# control_board.net
KiCad netlist of a schematic drawn in EAGLE
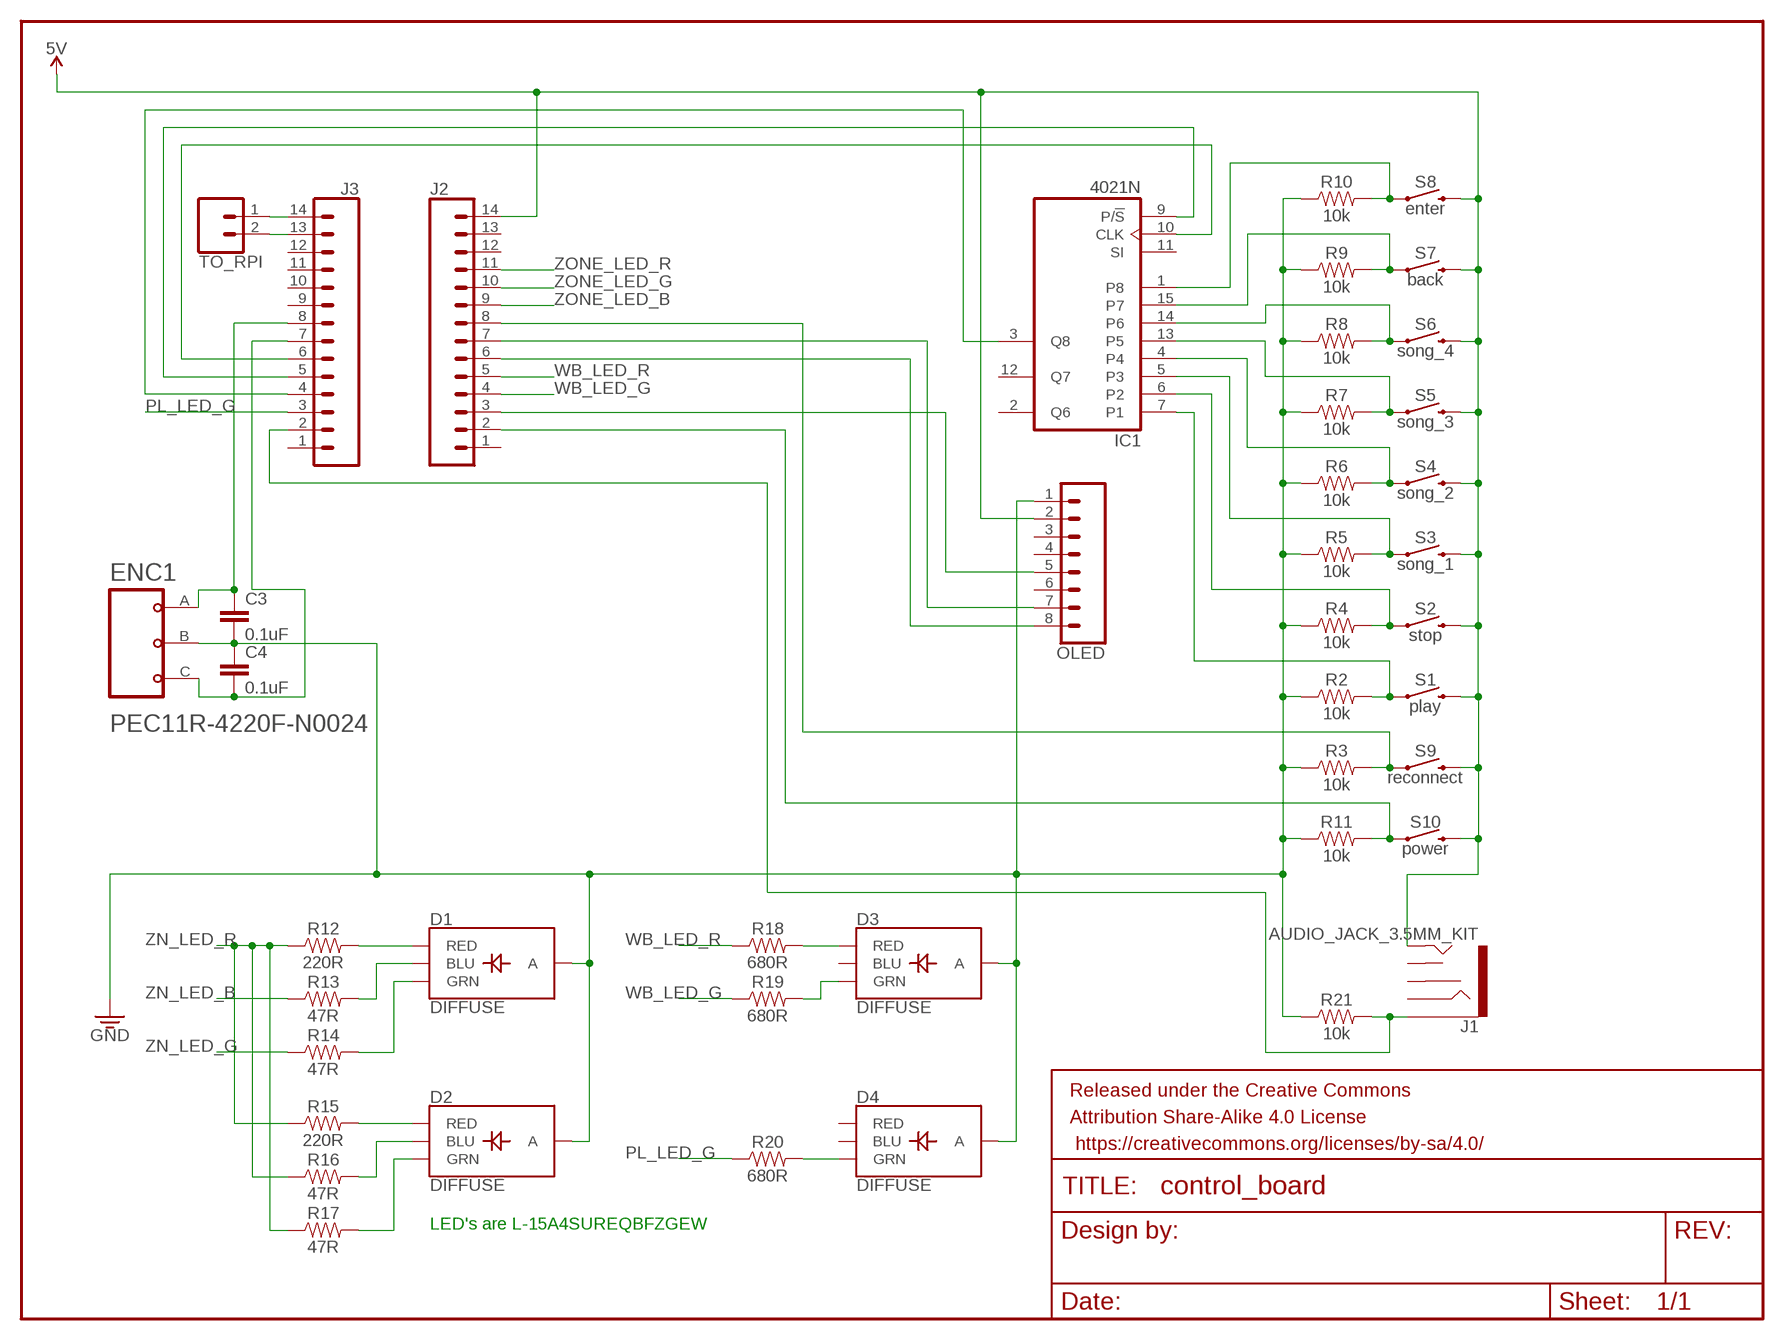
[diagram p0: schematic, sheet 1]

(export (version "E")
  (design (tool "Eeschema 10.0.6"))
  (components
    (comp (ref "C3")
      (value "0.1uF")
      (footprint "eagle-import:CAP-PTH-SMALL-KIT")
      (libsource (lib "eagle-import") (part "0.1UF-KIT-EZ-50V-20%"))
    )
    (comp (ref "C4")
      (value "0.1uF")
      (footprint "eagle-import:CAP-PTH-SMALL-KIT")
      (libsource (lib "eagle-import") (part "0.1UF-KIT-EZ-50V-20%"))
    )
    (comp (ref "D1")
      (value "DIFFUSE")
      (footprint "eagle-import:LED-RGB-THRU")
      (libsource (lib "eagle-import") (part "LED-RGB-CADIFFUSE"))
    )
    (comp (ref "D2")
      (value "DIFFUSE")
      (footprint "eagle-import:LED-RGB-THRU")
      (libsource (lib "eagle-import") (part "LED-RGB-CADIFFUSE"))
    )
    (comp (ref "D3")
      (value "DIFFUSE")
      (footprint "eagle-import:LED-RGB-THRU")
      (libsource (lib "eagle-import") (part "LED-RGB-CADIFFUSE"))
    )
    (comp (ref "D4")
      (value "DIFFUSE")
      (footprint "eagle-import:LED-RGB-THRU")
      (libsource (lib "eagle-import") (part "LED-RGB-CADIFFUSE"))
    )
    (comp (ref "ENC1")
      (value "PEC11R-4220F-N0024")
      (footprint "eagle-import:PEC11R-4220F-N0024")
      (libsource (lib "eagle-import") (part "PEC11R-4220F-N0024"))
    )
    (comp (ref "FRAME1")
      (value "FRAME-LETTER")
      (footprint "eagle-import:CREATIVE_COMMONS")
      (libsource (lib "eagle-import") (part "FRAME-LETTER"))
    )
    (comp (ref "IC1")
      (value "4021N")
      (footprint "eagle-import:DIL16")
      (libsource (lib "eagle-import") (part "4021N"))
    )
    (comp (ref "J1")
      (value "AUDIO_JACK_3.5MM_KIT")
      (footprint "eagle-import:AUDIO-JACK-KIT")
      (libsource (lib "eagle-import") (part "AUDIO_JACK_3.5MM_KIT"))
    )
    (comp (ref "J2")
      (value "CONN_14")
      (footprint "eagle-import:1X14")
      (libsource (lib "eagle-import") (part "CONN_14"))
    )
    (comp (ref "J3")
      (value "CONN_14")
      (footprint "eagle-import:1X14")
      (libsource (lib "eagle-import") (part "CONN_14"))
    )
    (comp (ref "OLED")
      (value "CONN_08\"")
      (footprint "eagle-import:1X08")
      (libsource (lib "eagle-import") (part "CONN_08{dblquote}"))
    )
    (comp (ref "R2")
      (value "10k")
      (footprint "eagle-import:AXIAL-0.3")
      (libsource (lib "eagle-import") (part "10KOHM-HORIZ-1/4W-1%"))
    )
    (comp (ref "R3")
      (value "10k")
      (footprint "eagle-import:AXIAL-0.3")
      (libsource (lib "eagle-import") (part "10KOHM-HORIZ-1/4W-1%"))
    )
    (comp (ref "R4")
      (value "10k")
      (footprint "eagle-import:AXIAL-0.3")
      (libsource (lib "eagle-import") (part "10KOHM-HORIZ-1/4W-1%"))
    )
    (comp (ref "R5")
      (value "10k")
      (footprint "eagle-import:AXIAL-0.3")
      (libsource (lib "eagle-import") (part "10KOHM-HORIZ-1/4W-1%"))
    )
    (comp (ref "R6")
      (value "10k")
      (footprint "eagle-import:AXIAL-0.3")
      (libsource (lib "eagle-import") (part "10KOHM-HORIZ-1/4W-1%"))
    )
    (comp (ref "R7")
      (value "10k")
      (footprint "eagle-import:AXIAL-0.3")
      (libsource (lib "eagle-import") (part "10KOHM-HORIZ-1/4W-1%"))
    )
    (comp (ref "R8")
      (value "10k")
      (footprint "eagle-import:AXIAL-0.3")
      (libsource (lib "eagle-import") (part "10KOHM-HORIZ-1/4W-1%"))
    )
    (comp (ref "R9")
      (value "10k")
      (footprint "eagle-import:AXIAL-0.3")
      (libsource (lib "eagle-import") (part "10KOHM-HORIZ-1/4W-1%"))
    )
    (comp (ref "R10")
      (value "10k")
      (footprint "eagle-import:AXIAL-0.3")
      (libsource (lib "eagle-import") (part "10KOHM-HORIZ-1/4W-1%"))
    )
    (comp (ref "R11")
      (value "10k")
      (footprint "eagle-import:AXIAL-0.3")
      (libsource (lib "eagle-import") (part "10KOHM-HORIZ-1/4W-1%"))
    )
    (comp (ref "R12")
      (value "220R")
      (footprint "eagle-import:AXIAL-0.3")
      (libsource (lib "eagle-import") (part "100OHM-HORIZ-1/4W-1%"))
    )
    (comp (ref "R13")
      (value "47R")
      (footprint "eagle-import:AXIAL-0.3")
      (libsource (lib "eagle-import") (part "100OHM-HORIZ-1/4W-1%"))
    )
    (comp (ref "R14")
      (value "47R")
      (footprint "eagle-import:AXIAL-0.3")
      (libsource (lib "eagle-import") (part "100OHM-HORIZ-1/4W-1%"))
    )
    (comp (ref "R15")
      (value "220R")
      (footprint "eagle-import:AXIAL-0.3")
      (libsource (lib "eagle-import") (part "100OHM-HORIZ-1/4W-1%"))
    )
    (comp (ref "R16")
      (value "47R")
      (footprint "eagle-import:AXIAL-0.3")
      (libsource (lib "eagle-import") (part "100OHM-HORIZ-1/4W-1%"))
    )
    (comp (ref "R17")
      (value "47R")
      (footprint "eagle-import:AXIAL-0.3")
      (libsource (lib "eagle-import") (part "100OHM-HORIZ-1/4W-1%"))
    )
    (comp (ref "R18")
      (value "680R")
      (footprint "eagle-import:AXIAL-0.3")
      (libsource (lib "eagle-import") (part "100OHM-HORIZ-1/4W-1%"))
    )
    (comp (ref "R19")
      (value "680R")
      (footprint "eagle-import:AXIAL-0.3")
      (libsource (lib "eagle-import") (part "100OHM-HORIZ-1/4W-1%"))
    )
    (comp (ref "R20")
      (value "680R")
      (footprint "eagle-import:AXIAL-0.3")
      (libsource (lib "eagle-import") (part "100OHM-HORIZ-1/4W-1%"))
    )
    (comp (ref "R21")
      (value "10k")
      (footprint "eagle-import:AXIAL-0.3")
      (libsource (lib "eagle-import") (part "10KOHM-HORIZ-1/4W-1%"))
    )
    (comp (ref "S1")
      (value "play")
      (footprint "eagle-import:TACTILE_SWITCH_PTH_6.0MM")
      (libsource (lib "eagle-import") (part "MOMENTARY-SWITCH-SPST-PTH-6.0MM"))
    )
    (comp (ref "S2")
      (value "stop")
      (footprint "eagle-import:TACTILE_SWITCH_PTH_6.0MM")
      (libsource (lib "eagle-import") (part "MOMENTARY-SWITCH-SPST-PTH-6.0MM"))
    )
    (comp (ref "S3")
      (value "song_1")
      (footprint "eagle-import:TACTILE_SWITCH_PTH_6.0MM")
      (libsource (lib "eagle-import") (part "MOMENTARY-SWITCH-SPST-PTH-6.0MM"))
    )
    (comp (ref "S4")
      (value "song_2")
      (footprint "eagle-import:TACTILE_SWITCH_PTH_6.0MM")
      (libsource (lib "eagle-import") (part "MOMENTARY-SWITCH-SPST-PTH-6.0MM"))
    )
    (comp (ref "S5")
      (value "song_3")
      (footprint "eagle-import:TACTILE_SWITCH_PTH_6.0MM")
      (libsource (lib "eagle-import") (part "MOMENTARY-SWITCH-SPST-PTH-6.0MM"))
    )
    (comp (ref "S6")
      (value "song_4")
      (footprint "eagle-import:TACTILE_SWITCH_PTH_6.0MM")
      (libsource (lib "eagle-import") (part "MOMENTARY-SWITCH-SPST-PTH-6.0MM"))
    )
    (comp (ref "S7")
      (value "back")
      (footprint "eagle-import:TACTILE_SWITCH_PTH_6.0MM")
      (libsource (lib "eagle-import") (part "MOMENTARY-SWITCH-SPST-PTH-6.0MM"))
    )
    (comp (ref "S8")
      (value "enter")
      (footprint "eagle-import:TACTILE_SWITCH_PTH_6.0MM")
      (libsource (lib "eagle-import") (part "MOMENTARY-SWITCH-SPST-PTH-6.0MM"))
    )
    (comp (ref "S9")
      (value "reconnect")
      (footprint "eagle-import:TACTILE_SWITCH_PTH_6.0MM")
      (libsource (lib "eagle-import") (part "MOMENTARY-SWITCH-SPST-PTH-6.0MM"))
    )
    (comp (ref "S10")
      (value "power")
      (footprint "eagle-import:TACTILE_SWITCH_PTH_6.0MM")
      (libsource (lib "eagle-import") (part "MOMENTARY-SWITCH-SPST-PTH-6.0MM"))
    )
    (comp (ref "TO_RPI")
      (value "CONN_02")
      (footprint "eagle-import:1X02")
      (libsource (lib "eagle-import") (part "CONN_02"))
    )
  )
  (nets
    (net (code "1") (name "/PL_LED_G") (class "Default")
      (node (ref "J3") (pin "3") (pinfunction "3_3") (pintype "passive"))
      (node (ref "R20") (pin "P$1") (pinfunction "1_P$1") (pintype "passive"))
    )
    (net (code "2") (name "/WB_LED_G") (class "Default")
      (node (ref "J2") (pin "4") (pinfunction "4_4") (pintype "passive"))
      (node (ref "R19") (pin "P$1") (pinfunction "1_P$1") (pintype "passive"))
    )
    (net (code "3") (name "/WB_LED_R") (class "Default")
      (node (ref "J2") (pin "5") (pinfunction "5_5") (pintype "passive"))
      (node (ref "R18") (pin "P$1") (pinfunction "1_P$1") (pintype "passive"))
    )
    (net (code "4") (name "/ZN_LED_B") (class "Default")
      (node (ref "R13") (pin "P$1") (pinfunction "1_P$1") (pintype "passive"))
    )
    (net (code "5") (name "/ZN_LED_G") (class "Default")
      (node (ref "R14") (pin "P$1") (pinfunction "1_P$1") (pintype "passive"))
    )
    (net (code "6") (name "/ZN_LED_R") (class "Default")
      (node (ref "R12") (pin "P$1") (pinfunction "1_P$1") (pintype "passive"))
      (node (ref "R15") (pin "P$1") (pinfunction "1_P$1") (pintype "passive"))
      (node (ref "R16") (pin "P$1") (pinfunction "1_P$1") (pintype "passive"))
      (node (ref "R17") (pin "P$1") (pinfunction "1_P$1") (pintype "passive"))
    )
    (net (code "7") (name "/ZONE_LED_B") (class "Default")
      (node (ref "J2") (pin "9") (pinfunction "9_9") (pintype "passive"))
    )
    (net (code "8") (name "/ZONE_LED_G") (class "Default")
      (node (ref "J2") (pin "10") (pinfunction "10_10") (pintype "passive"))
    )
    (net (code "9") (name "/ZONE_LED_R") (class "Default")
      (node (ref "J2") (pin "11") (pinfunction "11_11") (pintype "passive"))
    )
    (net (code "10") (name "5V") (class "Default")
      (node (ref "J1") (pin "TIP") (pinfunction "TIP_TIP") (pintype "bidirectional"))
      (node (ref "J2") (pin "14") (pinfunction "14_14") (pintype "passive"))
      (node (ref "OLED") (pin "2") (pinfunction "2_2") (pintype "passive"))
      (node (ref "S1") (pin "3") (pinfunction "2_3") (pintype "passive"))
      (node (ref "S10") (pin "3") (pinfunction "2_3") (pintype "passive"))
      (node (ref "S2") (pin "3") (pinfunction "2_3") (pintype "passive"))
      (node (ref "S3") (pin "3") (pinfunction "2_3") (pintype "passive"))
      (node (ref "S4") (pin "3") (pinfunction "2_3") (pintype "passive"))
      (node (ref "S5") (pin "3") (pinfunction "2_3") (pintype "passive"))
      (node (ref "S6") (pin "3") (pinfunction "2_3") (pintype "passive"))
      (node (ref "S7") (pin "3") (pinfunction "2_3") (pintype "passive"))
      (node (ref "S8") (pin "3") (pinfunction "2_3") (pintype "passive"))
      (node (ref "S9") (pin "3") (pinfunction "2_3") (pintype "passive"))
    )
    (net (code "11") (name "GND") (class "Default")
      (node (ref "C3") (pin "2") (pinfunction "2_2") (pintype "passive"))
      (node (ref "C4") (pin "1") (pinfunction "1_1") (pintype "passive"))
      (node (ref "D1") (pin "2") (pinfunction "A_2") (pintype "bidirectional"))
      (node (ref "D2") (pin "2") (pinfunction "A_2") (pintype "bidirectional"))
      (node (ref "D3") (pin "2") (pinfunction "A_2") (pintype "bidirectional"))
      (node (ref "D4") (pin "2") (pinfunction "A_2") (pintype "bidirectional"))
      (node (ref "ENC1") (pin "B") (pinfunction "CHANNEL_B_B") (pintype "bidirectional"))
      (node (ref "OLED") (pin "1") (pinfunction "1_1") (pintype "passive"))
      (node (ref "R10") (pin "P$1") (pinfunction "1_P$1") (pintype "passive"))
      (node (ref "R11") (pin "P$1") (pinfunction "1_P$1") (pintype "passive"))
      (node (ref "R2") (pin "P$1") (pinfunction "1_P$1") (pintype "passive"))
      (node (ref "R21") (pin "P$1") (pinfunction "1_P$1") (pintype "passive"))
      (node (ref "R3") (pin "P$1") (pinfunction "1_P$1") (pintype "passive"))
      (node (ref "R4") (pin "P$1") (pinfunction "1_P$1") (pintype "passive"))
      (node (ref "R5") (pin "P$1") (pinfunction "1_P$1") (pintype "passive"))
      (node (ref "R6") (pin "P$1") (pinfunction "1_P$1") (pintype "passive"))
      (node (ref "R7") (pin "P$1") (pinfunction "1_P$1") (pintype "passive"))
      (node (ref "R8") (pin "P$1") (pinfunction "1_P$1") (pintype "passive"))
      (node (ref "R9") (pin "P$1") (pinfunction "1_P$1") (pintype "passive"))
    )
    (net (code "12") (name "Net-(D1-BLU)") (class "Default")
      (node (ref "D1") (pin "4") (pinfunction "BLU_4") (pintype "bidirectional"))
      (node (ref "R13") (pin "P$2") (pinfunction "2_P$2") (pintype "passive"))
    )
    (net (code "13") (name "Net-(D1-GRN)") (class "Default")
      (node (ref "D1") (pin "3") (pinfunction "GRN_3") (pintype "bidirectional"))
      (node (ref "R14") (pin "P$2") (pinfunction "2_P$2") (pintype "passive"))
    )
    (net (code "14") (name "Net-(D1-RED)") (class "Default")
      (node (ref "D1") (pin "1") (pinfunction "RED_1") (pintype "bidirectional"))
      (node (ref "R12") (pin "P$2") (pinfunction "2_P$2") (pintype "passive"))
    )
    (net (code "15") (name "Net-(D2-BLU)") (class "Default")
      (node (ref "D2") (pin "4") (pinfunction "BLU_4") (pintype "bidirectional"))
      (node (ref "R16") (pin "P$2") (pinfunction "2_P$2") (pintype "passive"))
    )
    (net (code "16") (name "Net-(D2-GRN)") (class "Default")
      (node (ref "D2") (pin "3") (pinfunction "GRN_3") (pintype "bidirectional"))
      (node (ref "R17") (pin "P$2") (pinfunction "2_P$2") (pintype "passive"))
    )
    (net (code "17") (name "Net-(D2-RED)") (class "Default")
      (node (ref "D2") (pin "1") (pinfunction "RED_1") (pintype "bidirectional"))
      (node (ref "R15") (pin "P$2") (pinfunction "2_P$2") (pintype "passive"))
    )
    (net (code "18") (name "Net-(D3-GRN)") (class "Default")
      (node (ref "D3") (pin "3") (pinfunction "GRN_3") (pintype "bidirectional"))
      (node (ref "R19") (pin "P$2") (pinfunction "2_P$2") (pintype "passive"))
    )
    (net (code "19") (name "Net-(D3-RED)") (class "Default")
      (node (ref "D3") (pin "1") (pinfunction "RED_1") (pintype "bidirectional"))
      (node (ref "R18") (pin "P$2") (pinfunction "2_P$2") (pintype "passive"))
    )
    (net (code "20") (name "Net-(D4-GRN)") (class "Default")
      (node (ref "D4") (pin "3") (pinfunction "GRN_3") (pintype "bidirectional"))
      (node (ref "R20") (pin "P$2") (pinfunction "2_P$2") (pintype "passive"))
    )
    (net (code "21") (name "Net-(ENC1-CHANNEL_A)") (class "Default")
      (node (ref "C3") (pin "1") (pinfunction "1_1") (pintype "passive"))
      (node (ref "ENC1") (pin "A") (pinfunction "CHANNEL_A_A") (pintype "bidirectional"))
      (node (ref "J3") (pin "8") (pinfunction "8_8") (pintype "passive"))
    )
    (net (code "22") (name "Net-(ENC1-COMMON)") (class "Default")
      (node (ref "C4") (pin "2") (pinfunction "2_2") (pintype "passive"))
      (node (ref "ENC1") (pin "C") (pinfunction "COMMON_C") (pintype "bidirectional"))
      (node (ref "J3") (pin "7") (pinfunction "7_7") (pintype "passive"))
    )
    (net (code "23") (name "Net-(IC1A-CLK)") (class "Default")
      (node (ref "IC1") (pin "10") (pinfunction "CLK_10") (pintype "input"))
      (node (ref "J3") (pin "6") (pinfunction "6_6") (pintype "passive"))
    )
    (net (code "24") (name "Net-(IC1A-P1)") (class "Default")
      (node (ref "IC1") (pin "7") (pinfunction "P1_7") (pintype "input"))
      (node (ref "R2") (pin "P$2") (pinfunction "2_P$2") (pintype "passive"))
      (node (ref "S1") (pin "1") (pinfunction "1_1") (pintype "passive"))
    )
    (net (code "25") (name "Net-(IC1A-P2)") (class "Default")
      (node (ref "IC1") (pin "6") (pinfunction "P2_6") (pintype "input"))
      (node (ref "R4") (pin "P$2") (pinfunction "2_P$2") (pintype "passive"))
      (node (ref "S2") (pin "1") (pinfunction "1_1") (pintype "passive"))
    )
    (net (code "26") (name "Net-(IC1A-P3)") (class "Default")
      (node (ref "IC1") (pin "5") (pinfunction "P3_5") (pintype "input"))
      (node (ref "R5") (pin "P$2") (pinfunction "2_P$2") (pintype "passive"))
      (node (ref "S3") (pin "1") (pinfunction "1_1") (pintype "passive"))
    )
    (net (code "27") (name "Net-(IC1A-P4)") (class "Default")
      (node (ref "IC1") (pin "4") (pinfunction "P4_4") (pintype "input"))
      (node (ref "R6") (pin "P$2") (pinfunction "2_P$2") (pintype "passive"))
      (node (ref "S4") (pin "1") (pinfunction "1_1") (pintype "passive"))
    )
    (net (code "28") (name "Net-(IC1A-P5)") (class "Default")
      (node (ref "IC1") (pin "13") (pinfunction "P5_13") (pintype "input"))
      (node (ref "R7") (pin "P$2") (pinfunction "2_P$2") (pintype "passive"))
      (node (ref "S5") (pin "1") (pinfunction "1_1") (pintype "passive"))
    )
    (net (code "29") (name "Net-(IC1A-P6)") (class "Default")
      (node (ref "IC1") (pin "14") (pinfunction "P6_14") (pintype "input"))
      (node (ref "R8") (pin "P$2") (pinfunction "2_P$2") (pintype "passive"))
      (node (ref "S6") (pin "1") (pinfunction "1_1") (pintype "passive"))
    )
    (net (code "30") (name "Net-(IC1A-P7)") (class "Default")
      (node (ref "IC1") (pin "15") (pinfunction "P7_15") (pintype "input"))
      (node (ref "R9") (pin "P$2") (pinfunction "2_P$2") (pintype "passive"))
      (node (ref "S7") (pin "1") (pinfunction "1_1") (pintype "passive"))
    )
    (net (code "31") (name "Net-(IC1A-P8)") (class "Default")
      (node (ref "IC1") (pin "1") (pinfunction "P8_1") (pintype "input"))
      (node (ref "R10") (pin "P$2") (pinfunction "2_P$2") (pintype "passive"))
      (node (ref "S8") (pin "1") (pinfunction "1_1") (pintype "passive"))
    )
    (net (code "32") (name "Net-(IC1A-P{slash}~{S})") (class "Default")
      (node (ref "IC1") (pin "9") (pinfunction "P/~{S}_9") (pintype "input"))
      (node (ref "J3") (pin "5") (pinfunction "5_5") (pintype "passive"))
    )
    (net (code "33") (name "Net-(IC1A-Q8)") (class "Default")
      (node (ref "IC1") (pin "3") (pinfunction "Q8_3") (pintype "output"))
      (node (ref "J3") (pin "4") (pinfunction "4_4") (pintype "passive"))
    )
    (net (code "34") (name "Net-(J2-Pad3)") (class "Default")
      (node (ref "J2") (pin "3") (pinfunction "3_3") (pintype "passive"))
      (node (ref "OLED") (pin "5") (pinfunction "5_5") (pintype "passive"))
    )
    (net (code "35") (name "Net-(J2-Pad6)") (class "Default")
      (node (ref "J2") (pin "6") (pinfunction "6_6") (pintype "passive"))
      (node (ref "OLED") (pin "8") (pinfunction "8_8") (pintype "passive"))
    )
    (net (code "36") (name "Net-(J2-Pad7)") (class "Default")
      (node (ref "J2") (pin "7") (pinfunction "7_7") (pintype "passive"))
      (node (ref "OLED") (pin "7") (pinfunction "7_7") (pintype "passive"))
    )
    (net (code "37") (name "Net-(J3-Pad13)") (class "Default")
      (node (ref "J3") (pin "13") (pinfunction "13_13") (pintype "passive"))
      (node (ref "TO_RPI") (pin "2") (pinfunction "2_2") (pintype "passive"))
    )
    (net (code "38") (name "Net-(J3-Pad14)") (class "Default")
      (node (ref "J3") (pin "14") (pinfunction "14_14") (pintype "passive"))
      (node (ref "TO_RPI") (pin "1") (pinfunction "1_1") (pintype "passive"))
    )
    (net (code "39") (name "Net-(R3-2)") (class "Default")
      (node (ref "J2") (pin "8") (pinfunction "8_8") (pintype "passive"))
      (node (ref "R3") (pin "P$2") (pinfunction "2_P$2") (pintype "passive"))
      (node (ref "S9") (pin "1") (pinfunction "1_1") (pintype "passive"))
    )
    (net (code "40") (name "Net-(R11-2)") (class "Default")
      (node (ref "J2") (pin "2") (pinfunction "2_2") (pintype "passive"))
      (node (ref "R11") (pin "P$2") (pinfunction "2_P$2") (pintype "passive"))
      (node (ref "S10") (pin "1") (pinfunction "1_1") (pintype "passive"))
    )
    (net (code "41") (name "Net-(R21-2)") (class "Default")
      (node (ref "J1") (pin "SLEEVE") (pinfunction "SLEEVE_SLEEVE") (pintype "bidirectional"))
      (node (ref "J3") (pin "2") (pinfunction "2_2") (pintype "passive"))
      (node (ref "R21") (pin "P$2") (pinfunction "2_P$2") (pintype "passive"))
    )
    (net (code "42") (name "unconnected-(D3-BLU-Pad4)") (class "Default")
      (node (ref "D3") (pin "4") (pinfunction "BLU_4") (pintype "bidirectional"))
    )
    (net (code "43") (name "unconnected-(D4-BLU-Pad4)") (class "Default")
      (node (ref "D4") (pin "4") (pinfunction "BLU_4") (pintype "bidirectional"))
    )
    (net (code "44") (name "unconnected-(D4-RED-Pad1)") (class "Default")
      (node (ref "D4") (pin "1") (pinfunction "RED_1") (pintype "bidirectional"))
    )
    (net (code "45") (name "unconnected-(IC1A-Q6-Pad2)") (class "Default")
      (node (ref "IC1") (pin "2") (pinfunction "Q6_2") (pintype "output"))
    )
    (net (code "46") (name "unconnected-(IC1A-Q7-Pad12)") (class "Default")
      (node (ref "IC1") (pin "12") (pinfunction "Q7_12") (pintype "output"))
    )
    (net (code "47") (name "unconnected-(IC1A-SI-Pad11)") (class "Default")
      (node (ref "IC1") (pin "11") (pinfunction "SI_11") (pintype "input"))
    )
    (net (code "48") (name "unconnected-(J1-PadRING)") (class "Default")
      (node (ref "J1") (pin "RING") (pinfunction "RING_RING") (pintype "bidirectional"))
    )
    (net (code "49") (name "unconnected-(J1-PadRSH)") (class "Default")
      (node (ref "J1") (pin "RSH") (pinfunction "RSH_RSH") (pintype "bidirectional"))
    )
    (net (code "50") (name "unconnected-(J1-PadTSH)") (class "Default")
      (node (ref "J1") (pin "TSH") (pinfunction "TSH_TSH") (pintype "bidirectional"))
    )
    (net (code "51") (name "unconnected-(J2-Pad1)") (class "Default")
      (node (ref "J2") (pin "1") (pinfunction "1_1") (pintype "passive"))
    )
    (net (code "52") (name "unconnected-(J2-Pad12)") (class "Default")
      (node (ref "J2") (pin "12") (pinfunction "12_12") (pintype "passive"))
    )
    (net (code "53") (name "unconnected-(J2-Pad13)") (class "Default")
      (node (ref "J2") (pin "13") (pinfunction "13_13") (pintype "passive"))
    )
    (net (code "54") (name "unconnected-(J3-Pad1)") (class "Default")
      (node (ref "J3") (pin "1") (pinfunction "1_1") (pintype "passive"))
    )
    (net (code "55") (name "unconnected-(J3-Pad9)") (class "Default")
      (node (ref "J3") (pin "9") (pinfunction "9_9") (pintype "passive"))
    )
    (net (code "56") (name "unconnected-(J3-Pad10)") (class "Default")
      (node (ref "J3") (pin "10") (pinfunction "10_10") (pintype "passive"))
    )
    (net (code "57") (name "unconnected-(J3-Pad11)") (class "Default")
      (node (ref "J3") (pin "11") (pinfunction "11_11") (pintype "passive"))
    )
    (net (code "58") (name "unconnected-(J3-Pad12)") (class "Default")
      (node (ref "J3") (pin "12") (pinfunction "12_12") (pintype "passive"))
    )
    (net (code "59") (name "unconnected-(OLED-Pad3)") (class "Default")
      (node (ref "OLED") (pin "3") (pinfunction "3_3") (pintype "passive"))
    )
    (net (code "60") (name "unconnected-(OLED-Pad4)") (class "Default")
      (node (ref "OLED") (pin "4") (pinfunction "4_4") (pintype "passive"))
    )
    (net (code "61") (name "unconnected-(OLED-Pad6)") (class "Default")
      (node (ref "OLED") (pin "6") (pinfunction "6_6") (pintype "passive"))
    )
  )
)
